# VC_Peripherals.net
KiCad netlist of a schematic drawn in Altium Designer
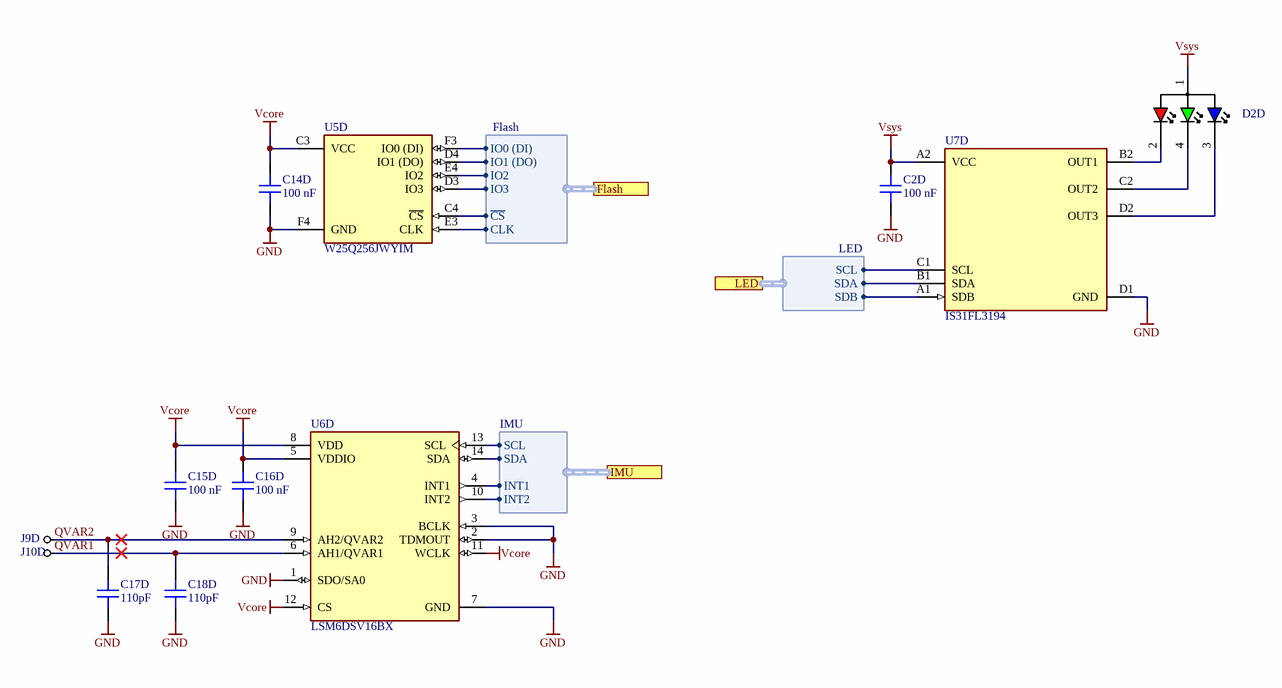
[diagram p0: VC_Peripherals.SchDoc]

(export (version "E")
  (design (tool "Eeschema 10.0.6"))
  (components
    (comp (ref "C2D")
      (value "100 nF")
      (footprint "VC_PCBLib:CAP_0201")
      (description "CAP CER 0.1UF 10V X5R 0201")
      (fields
        (field (name "MANUFACTURER") "Murata")
        (field (name "MANUFACTURER PART NUMBER") "GRM033Z71A104KE14D")
      )
      (libsource (lib "VC_SchematicLib") (part "CAP_0201_100n_10V"))
    )
    (comp (ref "C14D")
      (value "100 nF")
      (footprint "VC_PCBLib:CAP_0201")
      (description "CAP CER 0.1UF 10V X5R 0201")
      (fields
        (field (name "MANUFACTURER") "Murata")
        (field (name "MANUFACTURER PART NUMBER") "GRM033Z71A104KE14D")
      )
      (libsource (lib "VC_SchematicLib") (part "CAP_0201_100n_10V"))
    )
    (comp (ref "C15D")
      (value "100 nF")
      (footprint "VC_PCBLib:CAP_0201")
      (description "CAP CER 0.1UF 10V X5R 0201")
      (fields
        (field (name "MANUFACTURER") "Murata")
        (field (name "MANUFACTURER PART NUMBER") "GRM033Z71A104KE14D")
      )
      (libsource (lib "VC_SchematicLib") (part "CAP_0201_100n_10V"))
    )
    (comp (ref "C16D")
      (value "100 nF")
      (footprint "VC_PCBLib:CAP_0201")
      (description "CAP CER 0.1UF 10V X5R 0201")
      (fields
        (field (name "MANUFACTURER") "Murata")
        (field (name "MANUFACTURER PART NUMBER") "GRM033Z71A104KE14D")
      )
      (libsource (lib "VC_SchematicLib") (part "CAP_0201_100n_10V"))
    )
    (comp (ref "C17D")
      (value "110pF")
      (footprint "VC_PCBLib:CAP_0201")
      (description "CAP CER 110PF 50V C0G 0201")
      (fields
        (field (name "MANUFACTURER") "Murata")
        (field (name "MANUFACTURER PART NUMBER") "GRM0335C1H111JA01D")
      )
      (libsource (lib "VC_SchematicLib") (part "CAP_0201_110p_50V"))
    )
    (comp (ref "C18D")
      (value "110pF")
      (footprint "VC_PCBLib:CAP_0201")
      (description "CAP CER 110PF 50V C0G 0201")
      (fields
        (field (name "MANUFACTURER") "Murata")
        (field (name "MANUFACTURER PART NUMBER") "GRM0335C1H111JA01D")
      )
      (libsource (lib "VC_SchematicLib") (part "CAP_0201_110p_50V"))
    )
    (comp (ref "D2D")
      (value "SML-LX0404SIUPGUSB")
      (footprint "VC_PCBLib:SML-LX0404SIUPGUSB")
      (description "SML-LX0404SIUPGUSB RGB LED")
      (fields (field (name "MANUFACTURER") "Lumex"))
      (libsource (lib "VC_SchematicLib") (part "D_RGB_LED"))
    )
    (comp (ref "J9D")
      (value "PADSMD")
      (footprint "VC_PCBLib:PADSMD_ROUND")
      (description "SMD Pad")
      (libsource (lib "VC_SchematicLib") (part "PADSMD"))
    )
    (comp (ref "J10D")
      (value "PADSMD")
      (footprint "VC_PCBLib:PADSMD_ROUND")
      (description "SMD Pad")
      (libsource (lib "VC_SchematicLib") (part "PADSMD"))
    )
    (comp (ref "U5D")
      (value "W25Q256JWYIM")
      (footprint "VC_PCBLib:WLCSP_32_W25Q256JWYIM")
      (description "NOR-Flash spiFlash, 1.8V, 256M-bit, 4Kb Uniform Sector, DTR")
      (fields
        (field (name "MANUFACTURER PART NUMBER") "W25Q256JWYIM TR")
        (field (name "MANUFACTURER") "Winbond")
      )
      (libsource (lib "VC_SchematicLib") (part "W25Q256JWYIM"))
    )
    (comp (ref "U6D")
      (value "LSM6DSV16BX")
      (footprint "VC_PcbLib:LGA-14_STM")
      (description "IMU ACCEL/GYRO I2C/SPI 14LGA")
      (fields (field (name "MANUFACTURER") "STMicroelectronics"))
      (libsource (lib "VC_SchematicLib") (part "LSM6DSV16BX"))
    )
    (comp (ref "U7D")
      (value "IS31FL3194")
      (footprint "VC_PCBLib:WLCSP_8_P0.4")
      (description "LED Driver with Programmable Pattern Sequencing 3-Channel 40mA 8-Pin WCSP T/R")
      (fields
        (field (name "MANUFACTURER") "ISSI")
        (field (name "MANUFACTURER PART NUMBER") "IS31FL3194-CLS2-TR")
      )
      (libsource (lib "VC_SchematicLib") (part "IS31FL3194"))
    )
  )
  (nets
    (net (code "4") (name "/CLK") (class "Default")
      (node (ref "U5D") (pin "E3") (pinfunction "CLK_E3") (pintype "input"))
    )
    (net (code "5") (name "/INT1") (class "Default")
      (node (ref "U6D") (pin "4") (pinfunction "INT1_4") (pintype "output"))
    )
    (net (code "6") (name "/INT2") (class "Default")
      (node (ref "U6D") (pin "10") (pinfunction "INT2_10") (pintype "output"))
    )
    (net (code "7") (name "/IO0 (DI)") (class "Default")
      (node (ref "U5D") (pin "F3") (pinfunction "IO0_(DI)_F3") (pintype "bidirectional"))
    )
    (net (code "8") (name "/IO1 (DO)") (class "Default")
      (node (ref "U5D") (pin "D4") (pinfunction "IO1_(DO)_D4") (pintype "bidirectional"))
    )
    (net (code "9") (name "/IO2") (class "Default")
      (node (ref "U5D") (pin "E4") (pinfunction "IO2_E4") (pintype "bidirectional"))
    )
    (net (code "10") (name "/IO3") (class "Default")
      (node (ref "U5D") (pin "D3") (pinfunction "IO3_D3") (pintype "bidirectional"))
    )
    (net (code "11") (name "/QVAR1") (class "Default")
      (node (ref "C18D") (pin "2") (pinfunction "2_2") (pintype "passive"))
      (node (ref "J10D") (pin "0") (pintype "passive"))
      (node (ref "U6D") (pin "6") (pinfunction "AH1/QVAR1_6") (pintype "input"))
    )
    (net (code "12") (name "/QVAR2") (class "Default")
      (node (ref "C17D") (pin "2") (pinfunction "2_2") (pintype "passive"))
      (node (ref "J9D") (pin "0") (pintype "passive"))
      (node (ref "U6D") (pin "9") (pinfunction "AH2/QVAR2_9") (pintype "input"))
    )
    (net (code "13") (name "/SDB") (class "Default")
      (node (ref "U7D") (pin "A1") (pinfunction "SDB_A1") (pintype "input"))
    )
    (net (code "17") (name "/~{CS}") (class "Default")
      (node (ref "U5D") (pin "C4") (pinfunction "~{CS}_C4") (pintype "input"))
    )
    (net (code "18") (name "GND") (class "Default")
      (node (ref "C14D") (pin "1") (pinfunction "1_1") (pintype "passive"))
      (node (ref "C15D") (pin "1") (pinfunction "1_1") (pintype "passive"))
      (node (ref "C16D") (pin "1") (pinfunction "1_1") (pintype "passive"))
      (node (ref "C17D") (pin "1") (pinfunction "1_1") (pintype "passive"))
      (node (ref "C18D") (pin "1") (pinfunction "1_1") (pintype "passive"))
      (node (ref "C2D") (pin "1") (pinfunction "1_1") (pintype "passive"))
      (node (ref "U5D") (pin "F4") (pinfunction "GND_F4") (pintype "power_in"))
      (node (ref "U6D") (pin "1") (pinfunction "SDO/SA0_1") (pintype "bidirectional"))
      (node (ref "U6D") (pin "2") (pinfunction "TDMOUT_2") (pintype "bidirectional"))
      (node (ref "U6D") (pin "3") (pinfunction "BCLK_3") (pintype "input"))
      (node (ref "U6D") (pin "7") (pinfunction "GND_7") (pintype "power_in"))
      (node (ref "U7D") (pin "D1") (pinfunction "GND_D1") (pintype "power_in"))
    )
    (net (code "19") (name "Net-(D2D-Blue_C)") (class "Default")
      (node (ref "D2D") (pin "3") (pinfunction "Blue_C_3") (pintype "passive"))
      (node (ref "U7D") (pin "D2") (pinfunction "OUT3_D2") (pintype "open_collector"))
    )
    (net (code "20") (name "Net-(D2D-Green_C)") (class "Default")
      (node (ref "D2D") (pin "4") (pinfunction "Green_C_4") (pintype "passive"))
      (node (ref "U7D") (pin "C2") (pinfunction "OUT2_C2") (pintype "open_collector"))
    )
    (net (code "21") (name "Net-(D2D-Red_C)") (class "Default")
      (node (ref "D2D") (pin "2") (pinfunction "Red_C_2") (pintype "passive"))
      (node (ref "U7D") (pin "B2") (pinfunction "OUT1_B2") (pintype "open_collector"))
    )
    (net (code "22") (name "Vcore") (class "Default")
      (node (ref "C14D") (pin "2") (pinfunction "2_2") (pintype "passive"))
      (node (ref "C15D") (pin "2") (pinfunction "2_2") (pintype "passive"))
      (node (ref "C16D") (pin "2") (pinfunction "2_2") (pintype "passive"))
      (node (ref "U5D") (pin "C3") (pinfunction "VCC_C3") (pintype "power_in"))
      (node (ref "U6D") (pin "11") (pinfunction "WCLK_11") (pintype "bidirectional"))
      (node (ref "U6D") (pin "12") (pinfunction "CS_12") (pintype "input"))
      (node (ref "U6D") (pin "5") (pinfunction "VDDIO_5") (pintype "power_in"))
      (node (ref "U6D") (pin "8") (pinfunction "VDD_8") (pintype "power_in"))
    )
    (net (code "23") (name "Vsys") (class "Default")
      (node (ref "C2D") (pin "2") (pinfunction "2_2") (pintype "passive"))
      (node (ref "D2D") (pin "1") (pinfunction "Common_Anode_1") (pintype "passive"))
      (node (ref "U7D") (pin "A2") (pinfunction "VCC_A2") (pintype "power_in"))
    )
    (net (code "24") (name "unconnected-(U6D-SCL-Pad13)") (class "Default")
      (node (ref "U6D") (pin "13") (pinfunction "SCL_13") (pintype "input"))
    )
    (net (code "25") (name "unconnected-(U6D-SDA-Pad14)") (class "Default")
      (node (ref "U6D") (pin "14") (pinfunction "SDA_14") (pintype "bidirectional"))
    )
    (net (code "26") (name "unconnected-(U7D-SCL-PadC1)") (class "Default")
      (node (ref "U7D") (pin "C1") (pinfunction "SCL_C1") (pintype "open_collector"))
    )
    (net (code "27") (name "unconnected-(U7D-SDA-PadB1)") (class "Default")
      (node (ref "U7D") (pin "B1") (pinfunction "SDA_B1") (pintype "open_collector"))
    )
  )
)
